# C64-KeyboardTester.net
KiCad netlist of a schematic drawn in EAGLE
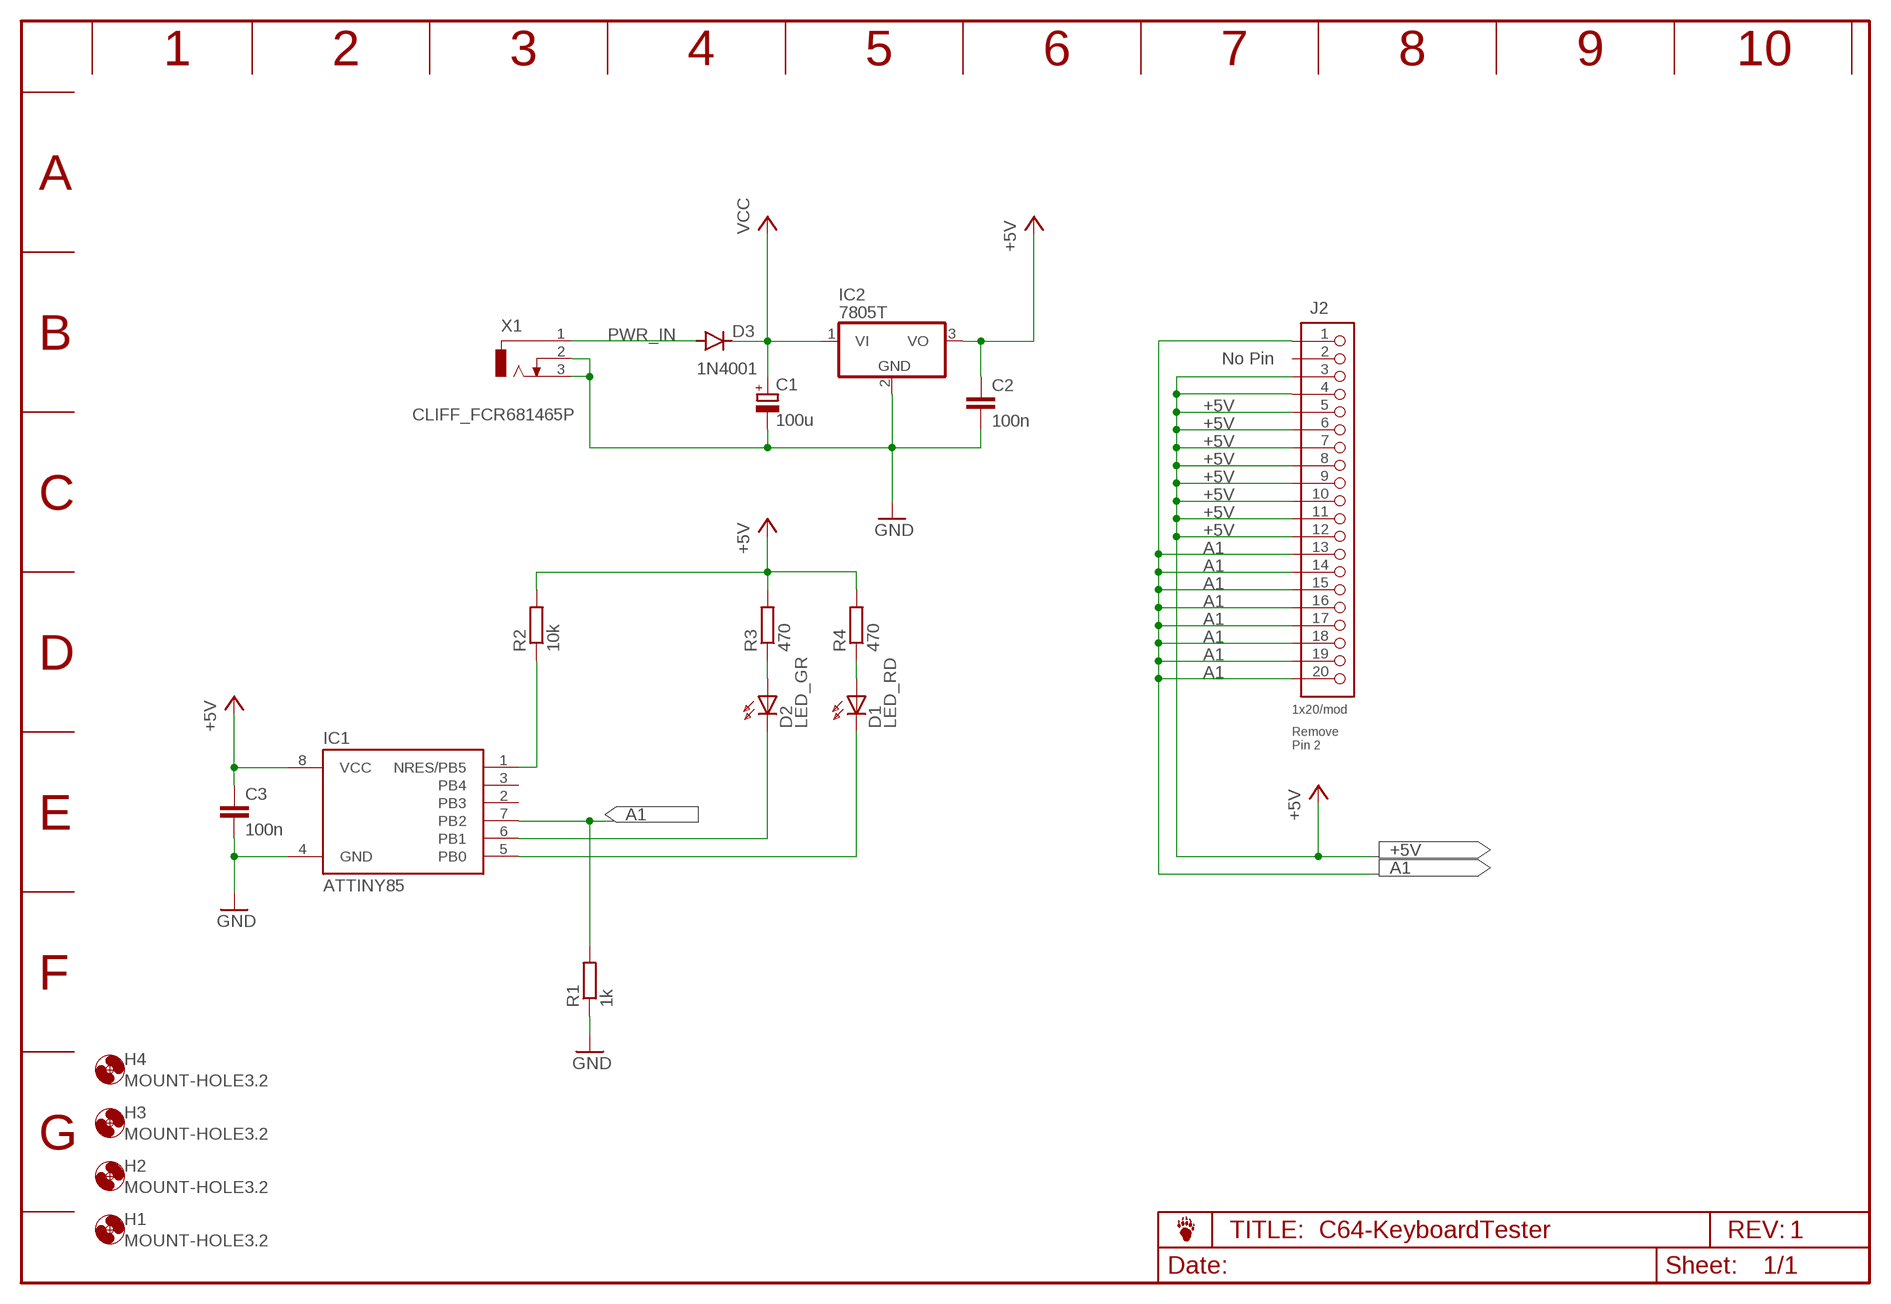
[diagram p0: schematic, sheet 1]

(export (version "E")
  (design (tool "Eeschema 10.0.6"))
  (components
    (comp (ref "C1")
      (value "100u")
      (footprint "eagle-import:E2,5-6")
      (libsource (lib "eagle-import") (part "CPOL-EUE2.5-6"))
    )
    (comp (ref "C2")
      (value "100n")
      (footprint "eagle-import:C025-024X044")
      (libsource (lib "eagle-import") (part "C-EU025-024X044"))
    )
    (comp (ref "C3")
      (value "100n")
      (footprint "eagle-import:C025-024X044")
      (libsource (lib "eagle-import") (part "C-EU025-024X044"))
    )
    (comp (ref "D1")
      (value "LED_RD")
      (footprint "eagle-import:LED3MM")
      (libsource (lib "eagle-import") (part "LED3MMS"))
    )
    (comp (ref "D2")
      (value "LED_GR")
      (footprint "eagle-import:LED3MM")
      (libsource (lib "eagle-import") (part "LED3MMS"))
    )
    (comp (ref "D3")
      (value "1N4001")
      (footprint "eagle-import:DO41-10")
      (libsource (lib "eagle-import") (part "1N4004"))
    )
    (comp (ref "H1")
      (value "MOUNT-HOLE3.2")
      (footprint "eagle-import:3,2")
      (libsource (lib "eagle-import") (part "MOUNT-HOLE3.2"))
    )
    (comp (ref "H2")
      (value "MOUNT-HOLE3.2")
      (footprint "eagle-import:3,2")
      (libsource (lib "eagle-import") (part "MOUNT-HOLE3.2"))
    )
    (comp (ref "H3")
      (value "MOUNT-HOLE3.2")
      (footprint "eagle-import:3,2")
      (libsource (lib "eagle-import") (part "MOUNT-HOLE3.2"))
    )
    (comp (ref "H4")
      (value "MOUNT-HOLE3.2")
      (footprint "eagle-import:3,2")
      (libsource (lib "eagle-import") (part "MOUNT-HOLE3.2"))
    )
    (comp (ref "IC1")
      (value "ATTINY85")
      (footprint "eagle-import:PDIP08_300MIL")
      (libsource (lib "eagle-import") (part "ATTINY85P-"))
    )
    (comp (ref "IC2")
      (value "7805T")
      (footprint "eagle-import:TO220H")
      (libsource (lib "eagle-import") (part "78T05"))
    )
    (comp (ref "J2")
      (value "1x20/mod")
      (footprint "eagle-import:1X20")
      (libsource (lib "eagle-import") (part "PINHD-1X20"))
    )
    (comp (ref "R1")
      (value "1k")
      (footprint "eagle-import:0207_10")
      (libsource (lib "eagle-import") (part "R-EU_0207/10"))
    )
    (comp (ref "R2")
      (value "10k")
      (footprint "eagle-import:0207_10")
      (libsource (lib "eagle-import") (part "R-EU_0207/10"))
    )
    (comp (ref "R3")
      (value "470")
      (footprint "eagle-import:0207_10")
      (libsource (lib "eagle-import") (part "R-EU_0207/10"))
    )
    (comp (ref "R4")
      (value "470")
      (footprint "eagle-import:0207_10")
      (libsource (lib "eagle-import") (part "R-EU_0207/10"))
    )
    (comp (ref "X1")
      (value "CLIFF_FCR681465P")
      (footprint "eagle-import:FCR681465P")
      (libsource (lib "eagle-import") (part "CLIFF_FCR681465P"))
    )
  )
  (nets
    (net (code "1") (name "+5V") (class "Default")
      (node (ref "C2") (pin "1") (pinfunction "1_1") (pintype "passive"))
      (node (ref "C3") (pin "1") (pinfunction "1_1") (pintype "passive"))
      (node (ref "IC1") (pin "8") (pinfunction "VCC_8") (pintype "power_in"))
      (node (ref "IC2") (pin "3") (pinfunction "VO_3") (pintype "passive"))
      (node (ref "J2") (pin "10") (pinfunction "10_10") (pintype "passive"))
      (node (ref "J2") (pin "11") (pinfunction "11_11") (pintype "passive"))
      (node (ref "J2") (pin "12") (pinfunction "12_12") (pintype "passive"))
      (node (ref "J2") (pin "3") (pinfunction "3_3") (pintype "passive"))
      (node (ref "J2") (pin "4") (pinfunction "4_4") (pintype "passive"))
      (node (ref "J2") (pin "5") (pinfunction "5_5") (pintype "passive"))
      (node (ref "J2") (pin "6") (pinfunction "6_6") (pintype "passive"))
      (node (ref "J2") (pin "7") (pinfunction "7_7") (pintype "passive"))
      (node (ref "J2") (pin "8") (pinfunction "8_8") (pintype "passive"))
      (node (ref "J2") (pin "9") (pinfunction "9_9") (pintype "passive"))
      (node (ref "R2") (pin "2") (pinfunction "2_2") (pintype "passive"))
      (node (ref "R3") (pin "2") (pinfunction "2_2") (pintype "passive"))
      (node (ref "R4") (pin "2") (pinfunction "2_2") (pintype "passive"))
    )
    (net (code "2") (name "/A1") (class "Default")
      (node (ref "IC1") (pin "7") (pinfunction "PB2_7") (pintype "bidirectional"))
      (node (ref "J2") (pin "1") (pinfunction "1_1") (pintype "passive"))
      (node (ref "J2") (pin "13") (pinfunction "13_13") (pintype "passive"))
      (node (ref "J2") (pin "14") (pinfunction "14_14") (pintype "passive"))
      (node (ref "J2") (pin "15") (pinfunction "15_15") (pintype "passive"))
      (node (ref "J2") (pin "16") (pinfunction "16_16") (pintype "passive"))
      (node (ref "J2") (pin "17") (pinfunction "17_17") (pintype "passive"))
      (node (ref "J2") (pin "18") (pinfunction "18_18") (pintype "passive"))
      (node (ref "J2") (pin "19") (pinfunction "19_19") (pintype "passive"))
      (node (ref "J2") (pin "20") (pinfunction "20_20") (pintype "passive"))
      (node (ref "R1") (pin "2") (pinfunction "2_2") (pintype "passive"))
    )
    (net (code "3") (name "/PWR_IN") (class "Default")
      (node (ref "D3") (pin "A") (pinfunction "A_A") (pintype "passive"))
      (node (ref "X1") (pin "1") (pinfunction "1_1") (pintype "passive"))
    )
    (net (code "4") (name "GND") (class "Default")
      (node (ref "C1") (pin "-") (pinfunction "-_-") (pintype "passive"))
      (node (ref "C2") (pin "2") (pinfunction "2_2") (pintype "passive"))
      (node (ref "C3") (pin "2") (pinfunction "2_2") (pintype "passive"))
      (node (ref "IC1") (pin "4") (pinfunction "GND_4") (pintype "power_in"))
      (node (ref "IC2") (pin "2") (pinfunction "GND_2") (pintype "passive"))
      (node (ref "R1") (pin "1") (pinfunction "1_1") (pintype "passive"))
      (node (ref "X1") (pin "2") (pinfunction "2_2") (pintype "passive"))
      (node (ref "X1") (pin "3") (pinfunction "3_3") (pintype "passive"))
    )
    (net (code "5") (name "Net-(D1-C)") (class "Default")
      (node (ref "D1") (pin "K") (pinfunction "C_K") (pintype "passive"))
      (node (ref "IC1") (pin "5") (pinfunction "PB0_5") (pintype "bidirectional"))
    )
    (net (code "6") (name "Net-(D1-PadA)") (class "Default")
      (node (ref "D1") (pin "A") (pinfunction "A_A") (pintype "passive"))
      (node (ref "R4") (pin "1") (pinfunction "1_1") (pintype "passive"))
    )
    (net (code "7") (name "Net-(D2-C)") (class "Default")
      (node (ref "D2") (pin "K") (pinfunction "C_K") (pintype "passive"))
      (node (ref "IC1") (pin "6") (pinfunction "PB1_6") (pintype "bidirectional"))
    )
    (net (code "8") (name "Net-(D2-PadA)") (class "Default")
      (node (ref "D2") (pin "A") (pinfunction "A_A") (pintype "passive"))
      (node (ref "R3") (pin "1") (pinfunction "1_1") (pintype "passive"))
    )
    (net (code "9") (name "Net-(IC1-NRES{slash}PB5)") (class "Default")
      (node (ref "IC1") (pin "1") (pinfunction "NRES/PB5_1") (pintype "bidirectional"))
      (node (ref "R2") (pin "1") (pinfunction "1_1") (pintype "passive"))
    )
    (net (code "10") (name "VCC") (class "Default")
      (node (ref "C1") (pin "+") (pinfunction "+_+") (pintype "passive"))
      (node (ref "D3") (pin "C") (pinfunction "C_C") (pintype "passive"))
      (node (ref "IC2") (pin "1") (pinfunction "VI_1") (pintype "input"))
    )
    (net (code "11") (name "unconnected-(IC1-PB3-Pad2)") (class "Default")
      (node (ref "IC1") (pin "2") (pinfunction "PB3_2") (pintype "bidirectional"))
    )
    (net (code "12") (name "unconnected-(IC1-PB4-Pad3)") (class "Default")
      (node (ref "IC1") (pin "3") (pinfunction "PB4_3") (pintype "bidirectional"))
    )
    (net (code "13") (name "unconnected-(J2-Pad2)") (class "Default")
      (node (ref "J2") (pin "2") (pinfunction "2_2") (pintype "passive"))
    )
  )
)
